# Sheet1.net
KiCad netlist of a schematic drawn in Altium Designer
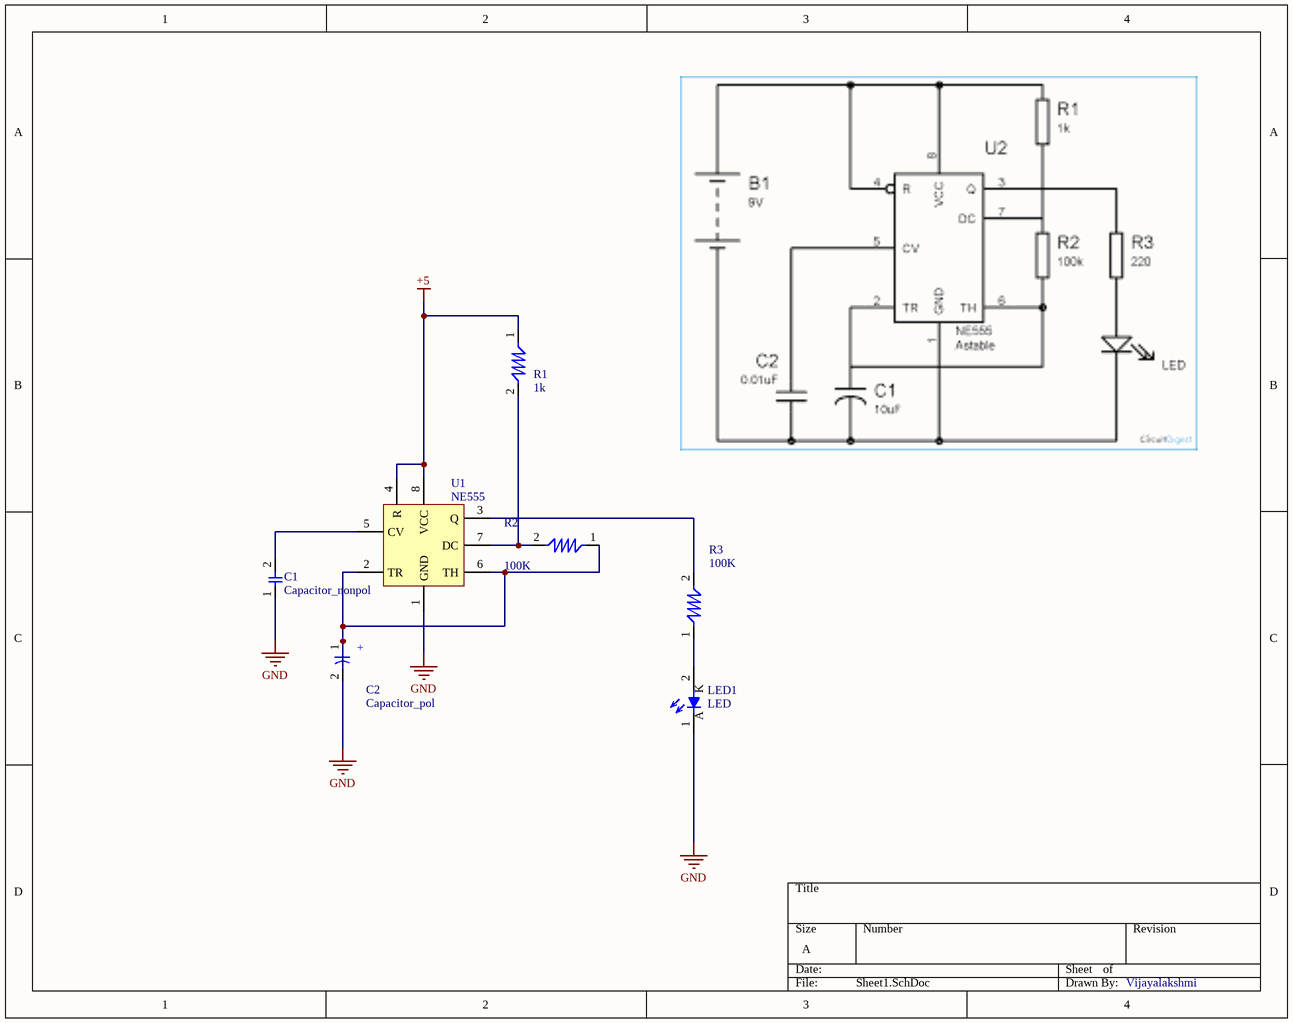
[diagram p0: Sheet1.SchDoc]

(export (version "E")
  (design (tool "Eeschema 10.0.6"))
  (components
    (comp (ref "C1")
      (value "Capacitor_nonpol")
      (footprint "CAPACITOR")
      (libsource (lib "LED BLINKING") (part "Capacitor_nonpol"))
    )
    (comp (ref "C2")
      (value "Capacitor_pol")
      (footprint "CAPACITOR")
      (libsource (lib "LED BLINKING") (part "Capacitor_pol"))
    )
    (comp (ref "LED1") (value "LED") (footprint "LED") (libsource (lib "LED BLINKING") (part "LED")))
    (comp (ref "R1")
      (value "1k")
      (footprint "restsror")
      (description "1 kOhms ±1% 0.1W, 1/10W Chip Resistor 0603 (1608 Metric) Automotive AEC-Q200 Thick Film")
      (fields
        (field (name "PART NUMBER") "RMCF0603FT1K00")
        (field (name "MANUFACTURER") "Stackpole Electronics Inc")
      )
      (libsource (lib "LED BLINKING") (part "1K/0.1W"))
    )
    (comp (ref "R2")
      (value "100K")
      (footprint "restsror")
      (libsource (lib "LED BLINKING") (part "100K/0.1W"))
    )
    (comp (ref "R3")
      (value "100K")
      (footprint "restsror")
      (libsource (lib "LED BLINKING") (part "100K/0.1W"))
    )
    (comp (ref "U1") (value "NE555") (footprint "IC") (libsource (lib "LED BLINKING") (part "NE555")))
  )
  (nets
    (net (code "1") (name "+5") (class "Default")
      (node (ref "R1") (pin "1") (pinfunction "1_1") (pintype "passive"))
      (node (ref "U1") (pin "4") (pinfunction "R_4") (pintype "passive"))
      (node (ref "U1") (pin "8") (pinfunction "VCC_8") (pintype "passive"))
    )
    (net (code "2") (name "GND") (class "Default")
      (node (ref "C1") (pin "1") (pinfunction "1_1") (pintype "passive"))
      (node (ref "C2") (pin "2") (pinfunction "-_2") (pintype "passive"))
      (node (ref "LED1") (pin "1") (pinfunction "A(+)_1") (pintype "passive"))
      (node (ref "U1") (pin "1") (pinfunction "GND_1") (pintype "passive"))
    )
    (net (code "3") (name "Net-(C2-+)") (class "Default")
      (node (ref "C2") (pin "1") (pinfunction "+_1") (pintype "passive"))
      (node (ref "R2") (pin "1") (pinfunction "1_1") (pintype "passive"))
      (node (ref "U1") (pin "2") (pinfunction "TR_2") (pintype "passive"))
      (node (ref "U1") (pin "6") (pinfunction "TH_6") (pintype "passive"))
    )
    (net (code "4") (name "Net-(LED1-K(-))") (class "Default")
      (node (ref "LED1") (pin "2") (pinfunction "K(-)_2") (pintype "passive"))
      (node (ref "R3") (pin "1") (pinfunction "1_1") (pintype "passive"))
    )
    (net (code "5") (name "Net-(U1-CV)") (class "Default")
      (node (ref "C1") (pin "2") (pinfunction "2_2") (pintype "passive"))
      (node (ref "U1") (pin "5") (pinfunction "CV_5") (pintype "passive"))
    )
    (net (code "6") (name "Net-(U1-DC)") (class "Default")
      (node (ref "R1") (pin "2") (pinfunction "2_2") (pintype "passive"))
      (node (ref "R2") (pin "2") (pinfunction "2_2") (pintype "passive"))
      (node (ref "U1") (pin "7") (pinfunction "DC_7") (pintype "passive"))
    )
    (net (code "7") (name "Net-(U1-Q)") (class "Default")
      (node (ref "R3") (pin "2") (pinfunction "2_2") (pintype "passive"))
      (node (ref "U1") (pin "3") (pinfunction "Q_3") (pintype "passive"))
    )
  )
)
